# DRV8711_BOARD.net
KiCad netlist of a schematic drawn in EAGLE
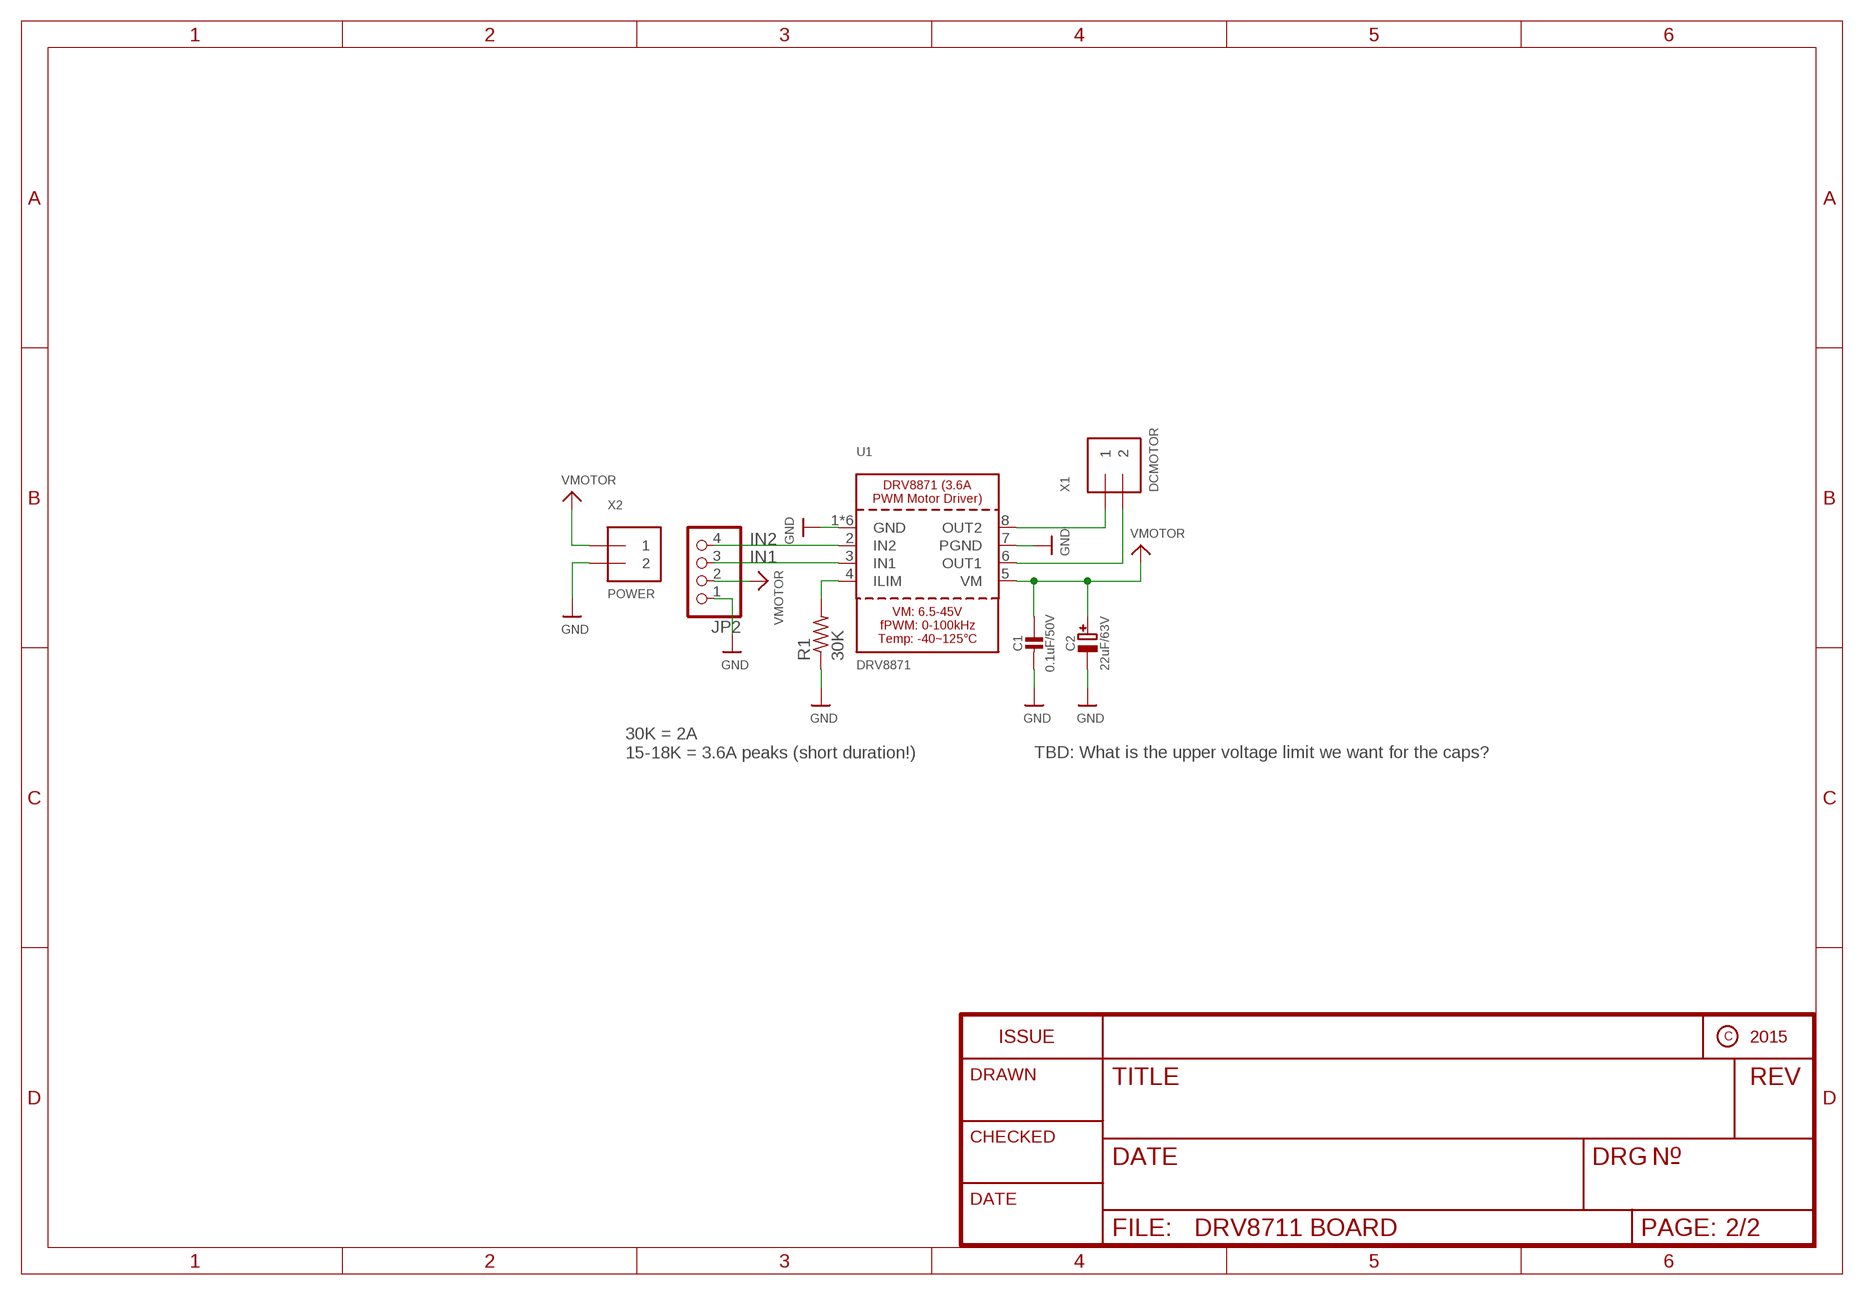
[diagram p0: schematic, sheet 2]

(export (version "E")
  (design (tool "Eeschema 10.0.6"))
  (components
    (comp (ref "C1")
      (value "0.1uF/50V")
      (footprint "eagle-import:0805-NO")
      (libsource (lib "eagle-import") (part "CAP_CERAMIC0805-NOOUTLINE"))
    )
    (comp (ref "C2")
      (value "22uF/63V")
      (footprint "eagle-import:CELEC_3.5MM_10MM")
      (libsource (lib "eagle-import") (part "CAP_ELECTROLYTICPTH_3.5MMGRID_10MMDIA"))
    )
    (comp (ref "JP2")
      (value "HEADER-1X476MIL")
      (footprint "eagle-import:1X04_ROUND_76")
      (libsource (lib "eagle-import") (part "HEADER-1X476MIL"))
    )
    (comp (ref "R1")
      (value "30K")
      (footprint "eagle-import:0805-THM")
      (libsource (lib "eagle-import") (part "FLIPFLOP-RES"))
    )
    (comp (ref "U1")
      (value "DRV8871")
      (footprint "eagle-import:HSOP8")
      (libsource (lib "eagle-import") (part "DRV8871"))
    )
    (comp (ref "X1")
      (value "DCMOTOR")
      (footprint "eagle-import:TERMBLOCK_1X2-3.5MM")
      (libsource (lib "eagle-import") (part "TERMBLOCK_1X2"))
    )
    (comp (ref "X2")
      (value "POWER")
      (footprint "eagle-import:TERMBLOCK_1X2-3.5MM")
      (libsource (lib "eagle-import") (part "TERMBLOCK_1X2"))
    )
  )
  (nets
    (net (code "1") (name "GND") (class "Default")
      (node (ref "C1") (pin "2") (pinfunction "2_2") (pintype "passive"))
      (node (ref "C2") (pin "-") (pinfunction "-_-") (pintype "passive"))
      (node (ref "JP2") (pin "1") (pinfunction "1_1") (pintype "passive"))
      (node (ref "R1") (pin "1") (pinfunction "1_1") (pintype "passive"))
      (node (ref "U1") (pin "1") (pinfunction "GND_1") (pintype "power_in"))
      (node (ref "U1") (pin "7") (pinfunction "PGND_7") (pintype "power_in"))
      (node (ref "U1") (pin "GND") (pinfunction "GND_GND") (pintype "power_in"))
      (node (ref "U1") (pin "P$1") (pinfunction "GND_P$1") (pintype "power_in"))
      (node (ref "U1") (pin "P$2") (pinfunction "GND_P$2") (pintype "power_in"))
      (node (ref "U1") (pin "P$3") (pinfunction "GND_P$3") (pintype "power_in"))
      (node (ref "U1") (pin "P$4") (pinfunction "GND_P$4") (pintype "power_in"))
      (node (ref "X2") (pin "2") (pinfunction "2_2") (pintype "passive"))
    )
    (net (code "2") (name "IN1") (class "Default")
      (node (ref "JP2") (pin "3") (pinfunction "3_3") (pintype "passive"))
      (node (ref "U1") (pin "3") (pinfunction "IN1_3") (pintype "input"))
    )
    (net (code "3") (name "IN2") (class "Default")
      (node (ref "JP2") (pin "4") (pinfunction "4_4") (pintype "passive"))
      (node (ref "U1") (pin "2") (pinfunction "IN2_2") (pintype "input"))
    )
    (net (code "4") (name "Net-(U1-ILIM)") (class "Default")
      (node (ref "R1") (pin "2") (pinfunction "2_2") (pintype "passive"))
      (node (ref "U1") (pin "4") (pinfunction "ILIM_4") (pintype "input"))
    )
    (net (code "5") (name "Net-(U1-OUT1)") (class "Default")
      (node (ref "U1") (pin "6") (pinfunction "OUT1_6") (pintype "output"))
      (node (ref "X1") (pin "2") (pinfunction "2_2") (pintype "passive"))
    )
    (net (code "6") (name "Net-(U1-OUT2)") (class "Default")
      (node (ref "U1") (pin "8") (pinfunction "OUT2_8") (pintype "output"))
      (node (ref "X1") (pin "1") (pinfunction "1_1") (pintype "passive"))
    )
    (net (code "7") (name "VMOTOR") (class "Default")
      (node (ref "C1") (pin "1") (pinfunction "1_1") (pintype "passive"))
      (node (ref "C2") (pin "+") (pinfunction "+_+") (pintype "passive"))
      (node (ref "JP2") (pin "2") (pinfunction "2_2") (pintype "passive"))
      (node (ref "U1") (pin "5") (pinfunction "VM_5") (pintype "power_in"))
      (node (ref "X2") (pin "1") (pinfunction "1_1") (pintype "passive"))
    )
  )
)
